# H0DR9_Frontend.net
KiCad netlist of a schematic drawn in Altium Designer
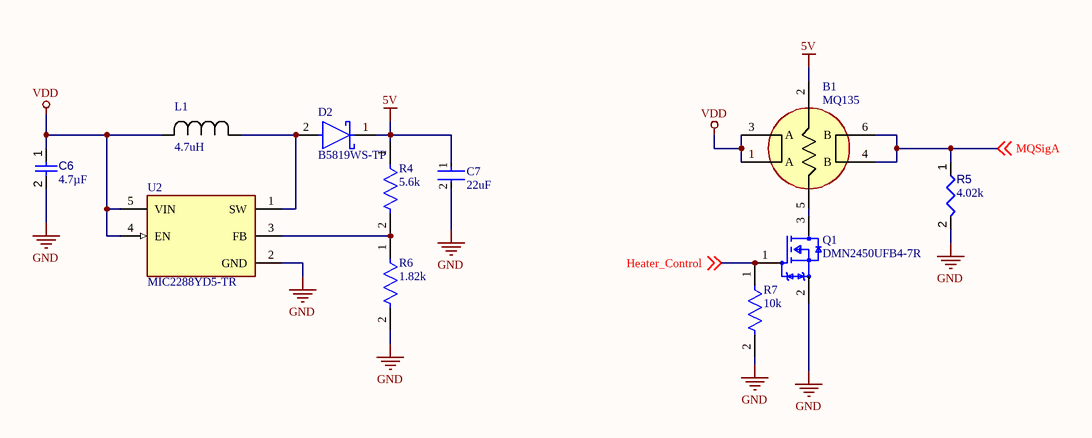
[diagram p0: H0DR9_Frontend.SchDoc]

(export (version "E")
  (design (tool "Eeschema 10.0.6"))
  (components
    (comp (ref "B1")
      (value "MQ135")
      (footprint "MQ135")
      (description "Sensor: gas; ammonia (NH3),benzene; Range: 1010000ppm; MQ-135")
      (libsource (lib "Duvan Boshoff") (part "MQ135"))
    )
    (comp (ref "C6")
      (value "4.7µF")
      (footprint "CAPC0603(1608)100_L")
      (description "Chip Capacitor, 4.7µF +/-20%, 10V, 0603, Thickness 1 mm")
      (fields (field (name "TOLERANCE") "10%") (field (name "Comment") "Capacitor 4.7µF +/-20% 10V 0603"))
      (libsource (lib "Duvan Boshoff") (part "CAP-NP-2"))
    )
    (comp (ref "C7")
      (value "22uF")
      (footprint "FP-GRM188-0_2-IPC_C")
      (description "Chip Multilayer Ceramic Capacitors for General Purpose, 0603, 22uF, X5R, 15%, 20%, 10V")
      (fields
        (field (name "TOLERANCE") "20%")
        (field (name "MANAFACTURING_PART_NUMBER") "GRM188R61A226ME15D")
      )
      (libsource (lib "Altium Content Vault") (part "11868f565c42a9108669ba33697ecf6"))
    )
    (comp (ref "D2")
      (value "B5819WS-TP")
      (footprint "FP-SOD-323-IPC_C")
      (description "DIODE SCHOTTKY 40V 1A SOD323")
      (fields (field (name "MANUFACTURER") "MCC") (field (name "MPN") "B5819WS-TR"))
      (libsource (lib "Altium Content Vault") (part "1d6ec82d83fb6aee721767c19dac4b9"))
    )
    (comp (ref "L1")
      (value "4.7uH")
      (footprint "IND_T4R7M_TAY")
      (description "No Description Available")
      (fields
        (field (name "MANUFACTURER_PART_NUMBER") "MBKK2012T4R7M")
        (field (name "COPYRIGHT") "Copyright (C) 2025 Ultra Librarian. All rights reserved.")
      )
      (libsource (lib "Duvan Boshoff") (part "MBKK2012T4R7M"))
    )
    (comp (ref "Q1")
      (value "DMN2450UFB4-7R")
      (footprint "FP-X2-DFN1006-3-MFG")
      (description "DMN2450UFB4-7R Trans Mosfet N-ch 20V 1A 3-PIN Dfn SMD T/r")
      (fields (field (name "MANUFACTURER") "Diodes Inc."))
      (libsource (lib "Altium Content Vault") (part "0c2281f89310cc54721de74d28721ba"))
    )
    (comp (ref "R4")
      (value "5.6k")
      (footprint "FP-RMCF0603-IPC_C")
      (description "5.6kΩ ±5% 0.1W 0603 Thick Film Chip Resistor AEC-Q200 compliant")
      (fields (field (name "TOLERANCE") "5%"))
      (libsource (lib "Altium Content Vault") (part "1029c3af85768c4190bb7ad29bc67b5"))
    )
    (comp (ref "R5")
      (value "4.02k")
      (footprint "RESC0402(1005)_L")
      (description "Chip Resistor, 4,02 kOhms, +/-1 %, 63 mW, -55 to 155 degC, 0402")
      (fields (field (name "POWER") "63mW") (field (name "TOLERANCE") "1%"))
      (libsource (lib "Duvan Boshoff") (part "RES-2"))
    )
    (comp (ref "R6")
      (value "1.82k")
      (footprint "FP-RT0603-MFG")
      (description "RES SMD 1.82K OHM 0.1% 1/10W")
      (fields
        (field (name "OCTOPART") "https://octopart.com/rt0603brd071k82l-yageo-1442926")
        (field (name "MANUFACTURER PART NUMBER") "RT0603BRD071K82L")
      )
      (libsource (lib "Altium Content Vault") (part "1029c3af85768c4190bb7ad29bc67b5"))
    )
    (comp (ref "R7")
      (value "10k")
      (footprint "FP-CRGCQ0603-IPC_C")
      (description "CRGCQ 0603 10K 5%")
      (fields
        (field (name "TOLERANCE") "0.05")
        (field (name "OCTOPART") "https://octopart.com/crgcq0603j10k-te+connectivity-91018097")
      )
      (libsource (lib "Altium Content Vault") (part "1029c3af85768c4190bb7ad29bc67b5"))
    )
    (comp (ref "U2")
      (value "MIC2288YD5-TR")
      (footprint "FP-TSOT-5LD-PL-1-MFG")
      (description "IC REG BOOST ADJ 1.2A TSOT23-5")
      (fields (field (name "MANUFACTURER") "Microchip"))
      (libsource (lib "Altium Content Vault") (part "8b40e419ffb951c8150a61de73387bc"))
    )
  )
  (nets
    (net (code "1") (name "5V") (class "Default")
      (node (ref "B1") (pin "2") (pinfunction "Heater_2") (pintype "passive"))
      (node (ref "C7") (pin "1") (pinfunction "1_1") (pintype "passive"))
      (node (ref "D2") (pin "1") (pinfunction "C_1") (pintype "passive"))
      (node (ref "R4") (pin "1") (pinfunction "1_1") (pintype "passive"))
    )
    (net (code "2") (name "GND") (class "Default")
      (node (ref "C6") (pin "2") (pinfunction "2_2") (pintype "passive"))
      (node (ref "C7") (pin "2") (pinfunction "2_2") (pintype "passive"))
      (node (ref "Q1") (pin "2") (pinfunction "S_2") (pintype "passive"))
      (node (ref "R5") (pin "2") (pinfunction "2_2") (pintype "passive"))
      (node (ref "R6") (pin "2") (pinfunction "2_2") (pintype "passive"))
      (node (ref "R7") (pin "2") (pinfunction "2_2") (pintype "passive"))
      (node (ref "U2") (pin "2") (pinfunction "GND_2") (pintype "power_in"))
    )
    (net (code "3") (name "Heater_Control") (class "Default")
      (node (ref "Q1") (pin "1") (pinfunction "G_1") (pintype "passive"))
      (node (ref "R7") (pin "1") (pinfunction "1_1") (pintype "passive"))
    )
    (net (code "4") (name "MQSigA") (class "Default")
      (node (ref "B1") (pin "4") (pinfunction "B_4") (pintype "passive"))
      (node (ref "B1") (pin "6") (pinfunction "B_6") (pintype "passive"))
      (node (ref "R5") (pin "1") (pinfunction "1_1") (pintype "passive"))
    )
    (net (code "5") (name "Net-(D2-A)") (class "Default")
      (node (ref "D2") (pin "2") (pinfunction "A_2") (pintype "passive"))
      (node (ref "L1") (pin "1") (pinfunction "1_1") (pintype "passive"))
      (node (ref "U2") (pin "1") (pinfunction "SW_1") (pintype "power_in"))
    )
    (net (code "6") (name "Net-(Q1-D)") (class "Default")
      (node (ref "B1") (pin "5") (pinfunction "Heater_5") (pintype "passive"))
      (node (ref "Q1") (pin "3") (pinfunction "D_3") (pintype "passive"))
    )
    (net (code "7") (name "Net-(U2-FB)") (class "Default")
      (node (ref "R4") (pin "2") (pinfunction "2_2") (pintype "passive"))
      (node (ref "R6") (pin "1") (pinfunction "1_1") (pintype "passive"))
      (node (ref "U2") (pin "3") (pinfunction "FB_3") (pintype "passive"))
    )
    (net (code "8") (name "VDD") (class "Default")
      (node (ref "B1") (pin "1") (pinfunction "A_1") (pintype "passive"))
      (node (ref "B1") (pin "3") (pinfunction "A_3") (pintype "passive"))
      (node (ref "C6") (pin "1") (pinfunction "1_1") (pintype "passive"))
      (node (ref "L1") (pin "2") (pinfunction "2_2") (pintype "passive"))
      (node (ref "U2") (pin "4") (pinfunction "EN_4") (pintype "input"))
      (node (ref "U2") (pin "5") (pinfunction "VIN_5") (pintype "power_in"))
    )
  )
)
